# rcz80test_v1.net
KiCad netlist of a schematic drawn in EAGLE
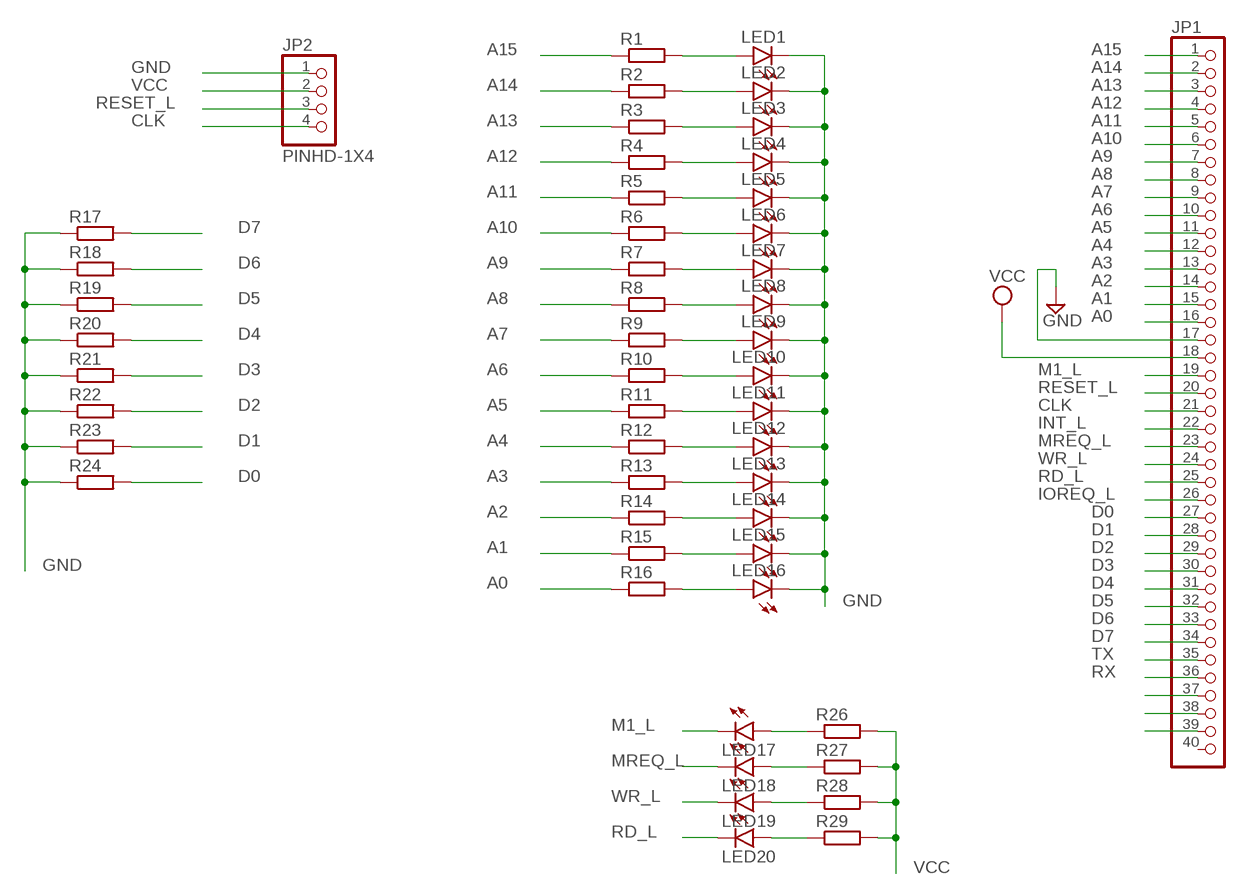
[diagram p0: schematic, sheet 1]

(export (version "E")
  (design (tool "Eeschema 10.0.6"))
  (components
    (comp (ref "JP1")
      (value "PINHD-1X40")
      (footprint "eagle-import:1X40")
      (libsource (lib "eagle-import") (part "PINHD-1X40"))
    )
    (comp (ref "JP2")
      (value "PINHD-1X4")
      (footprint "eagle-import:1X04")
      (libsource (lib "eagle-import") (part "PINHD-1X4"))
    )
    (comp (ref "LED1")
      (value "LED3MM")
      (footprint "eagle-import:LED3MM")
      (libsource (lib "eagle-import") (part "LED3MM"))
    )
    (comp (ref "LED2")
      (value "LED3MM")
      (footprint "eagle-import:LED3MM")
      (libsource (lib "eagle-import") (part "LED3MM"))
    )
    (comp (ref "LED3")
      (value "LED3MM")
      (footprint "eagle-import:LED3MM")
      (libsource (lib "eagle-import") (part "LED3MM"))
    )
    (comp (ref "LED4")
      (value "LED3MM")
      (footprint "eagle-import:LED3MM")
      (libsource (lib "eagle-import") (part "LED3MM"))
    )
    (comp (ref "LED5")
      (value "LED3MM")
      (footprint "eagle-import:LED3MM")
      (libsource (lib "eagle-import") (part "LED3MM"))
    )
    (comp (ref "LED6")
      (value "LED3MM")
      (footprint "eagle-import:LED3MM")
      (libsource (lib "eagle-import") (part "LED3MM"))
    )
    (comp (ref "LED7")
      (value "LED3MM")
      (footprint "eagle-import:LED3MM")
      (libsource (lib "eagle-import") (part "LED3MM"))
    )
    (comp (ref "LED8")
      (value "LED3MM")
      (footprint "eagle-import:LED3MM")
      (libsource (lib "eagle-import") (part "LED3MM"))
    )
    (comp (ref "LED9")
      (value "LED3MM")
      (footprint "eagle-import:LED3MM")
      (libsource (lib "eagle-import") (part "LED3MM"))
    )
    (comp (ref "LED10")
      (value "LED3MM")
      (footprint "eagle-import:LED3MM")
      (libsource (lib "eagle-import") (part "LED3MM"))
    )
    (comp (ref "LED11")
      (value "LED3MM")
      (footprint "eagle-import:LED3MM")
      (libsource (lib "eagle-import") (part "LED3MM"))
    )
    (comp (ref "LED12")
      (value "LED3MM")
      (footprint "eagle-import:LED3MM")
      (libsource (lib "eagle-import") (part "LED3MM"))
    )
    (comp (ref "LED13")
      (value "LED3MM")
      (footprint "eagle-import:LED3MM")
      (libsource (lib "eagle-import") (part "LED3MM"))
    )
    (comp (ref "LED14")
      (value "LED3MM")
      (footprint "eagle-import:LED3MM")
      (libsource (lib "eagle-import") (part "LED3MM"))
    )
    (comp (ref "LED15")
      (value "LED3MM")
      (footprint "eagle-import:LED3MM")
      (libsource (lib "eagle-import") (part "LED3MM"))
    )
    (comp (ref "LED16")
      (value "LED3MM")
      (footprint "eagle-import:LED3MM")
      (libsource (lib "eagle-import") (part "LED3MM"))
    )
    (comp (ref "LED17")
      (value "LED3MM")
      (footprint "eagle-import:LED3MM")
      (libsource (lib "eagle-import") (part "LED3MM"))
    )
    (comp (ref "LED18")
      (value "LED3MM")
      (footprint "eagle-import:LED3MM")
      (libsource (lib "eagle-import") (part "LED3MM"))
    )
    (comp (ref "LED19")
      (value "LED3MM")
      (footprint "eagle-import:LED3MM")
      (libsource (lib "eagle-import") (part "LED3MM"))
    )
    (comp (ref "LED20")
      (value "LED3MM")
      (footprint "eagle-import:LED3MM")
      (libsource (lib "eagle-import") (part "LED3MM"))
    )
    (comp (ref "R1")
      (value "R-EU_0204/7")
      (footprint "eagle-import:0204_7")
      (libsource (lib "eagle-import") (part "R-EU_0204/7"))
    )
    (comp (ref "R2")
      (value "R-EU_0204/7")
      (footprint "eagle-import:0204_7")
      (libsource (lib "eagle-import") (part "R-EU_0204/7"))
    )
    (comp (ref "R3")
      (value "R-EU_0204/7")
      (footprint "eagle-import:0204_7")
      (libsource (lib "eagle-import") (part "R-EU_0204/7"))
    )
    (comp (ref "R4")
      (value "R-EU_0204/7")
      (footprint "eagle-import:0204_7")
      (libsource (lib "eagle-import") (part "R-EU_0204/7"))
    )
    (comp (ref "R5")
      (value "R-EU_0204/7")
      (footprint "eagle-import:0204_7")
      (libsource (lib "eagle-import") (part "R-EU_0204/7"))
    )
    (comp (ref "R6")
      (value "R-EU_0204/7")
      (footprint "eagle-import:0204_7")
      (libsource (lib "eagle-import") (part "R-EU_0204/7"))
    )
    (comp (ref "R7")
      (value "R-EU_0204/7")
      (footprint "eagle-import:0204_7")
      (libsource (lib "eagle-import") (part "R-EU_0204/7"))
    )
    (comp (ref "R8")
      (value "R-EU_0204/7")
      (footprint "eagle-import:0204_7")
      (libsource (lib "eagle-import") (part "R-EU_0204/7"))
    )
    (comp (ref "R9")
      (value "R-EU_0204/7")
      (footprint "eagle-import:0204_7")
      (libsource (lib "eagle-import") (part "R-EU_0204/7"))
    )
    (comp (ref "R10")
      (value "R-EU_0204/7")
      (footprint "eagle-import:0204_7")
      (libsource (lib "eagle-import") (part "R-EU_0204/7"))
    )
    (comp (ref "R11")
      (value "R-EU_0204/7")
      (footprint "eagle-import:0204_7")
      (libsource (lib "eagle-import") (part "R-EU_0204/7"))
    )
    (comp (ref "R12")
      (value "R-EU_0204/7")
      (footprint "eagle-import:0204_7")
      (libsource (lib "eagle-import") (part "R-EU_0204/7"))
    )
    (comp (ref "R13")
      (value "R-EU_0204/7")
      (footprint "eagle-import:0204_7")
      (libsource (lib "eagle-import") (part "R-EU_0204/7"))
    )
    (comp (ref "R14")
      (value "R-EU_0204/7")
      (footprint "eagle-import:0204_7")
      (libsource (lib "eagle-import") (part "R-EU_0204/7"))
    )
    (comp (ref "R15")
      (value "R-EU_0204/7")
      (footprint "eagle-import:0204_7")
      (libsource (lib "eagle-import") (part "R-EU_0204/7"))
    )
    (comp (ref "R16")
      (value "R-EU_0204/7")
      (footprint "eagle-import:0204_7")
      (libsource (lib "eagle-import") (part "R-EU_0204/7"))
    )
    (comp (ref "R17")
      (value "R-EU_0204/7")
      (footprint "eagle-import:0204_7")
      (libsource (lib "eagle-import") (part "R-EU_0204/7"))
    )
    (comp (ref "R18")
      (value "R-EU_0204/7")
      (footprint "eagle-import:0204_7")
      (libsource (lib "eagle-import") (part "R-EU_0204/7"))
    )
    (comp (ref "R19")
      (value "R-EU_0204/7")
      (footprint "eagle-import:0204_7")
      (libsource (lib "eagle-import") (part "R-EU_0204/7"))
    )
    (comp (ref "R20")
      (value "R-EU_0204/7")
      (footprint "eagle-import:0204_7")
      (libsource (lib "eagle-import") (part "R-EU_0204/7"))
    )
    (comp (ref "R21")
      (value "R-EU_0204/7")
      (footprint "eagle-import:0204_7")
      (libsource (lib "eagle-import") (part "R-EU_0204/7"))
    )
    (comp (ref "R22")
      (value "R-EU_0204/7")
      (footprint "eagle-import:0204_7")
      (libsource (lib "eagle-import") (part "R-EU_0204/7"))
    )
    (comp (ref "R23")
      (value "R-EU_0204/7")
      (footprint "eagle-import:0204_7")
      (libsource (lib "eagle-import") (part "R-EU_0204/7"))
    )
    (comp (ref "R24")
      (value "R-EU_0204/7")
      (footprint "eagle-import:0204_7")
      (libsource (lib "eagle-import") (part "R-EU_0204/7"))
    )
    (comp (ref "R26")
      (value "R-EU_0204/7")
      (footprint "eagle-import:0204_7")
      (libsource (lib "eagle-import") (part "R-EU_0204/7"))
    )
    (comp (ref "R27")
      (value "R-EU_0204/7")
      (footprint "eagle-import:0204_7")
      (libsource (lib "eagle-import") (part "R-EU_0204/7"))
    )
    (comp (ref "R28")
      (value "R-EU_0204/7")
      (footprint "eagle-import:0204_7")
      (libsource (lib "eagle-import") (part "R-EU_0204/7"))
    )
    (comp (ref "R29")
      (value "R-EU_0204/7")
      (footprint "eagle-import:0204_7")
      (libsource (lib "eagle-import") (part "R-EU_0204/7"))
    )
  )
  (nets
    (net (code "1") (name "/A0") (class "Default")
      (node (ref "JP1") (pin "16") (pinfunction "16_16") (pintype "passive"))
      (node (ref "R16") (pin "1") (pinfunction "1_1") (pintype "passive"))
    )
    (net (code "2") (name "/A1") (class "Default")
      (node (ref "JP1") (pin "15") (pinfunction "15_15") (pintype "passive"))
      (node (ref "R15") (pin "1") (pinfunction "1_1") (pintype "passive"))
    )
    (net (code "3") (name "/A2") (class "Default")
      (node (ref "JP1") (pin "14") (pinfunction "14_14") (pintype "passive"))
      (node (ref "R14") (pin "1") (pinfunction "1_1") (pintype "passive"))
    )
    (net (code "4") (name "/A3") (class "Default")
      (node (ref "JP1") (pin "13") (pinfunction "13_13") (pintype "passive"))
      (node (ref "R13") (pin "1") (pinfunction "1_1") (pintype "passive"))
    )
    (net (code "5") (name "/A4") (class "Default")
      (node (ref "JP1") (pin "12") (pinfunction "12_12") (pintype "passive"))
      (node (ref "R12") (pin "1") (pinfunction "1_1") (pintype "passive"))
    )
    (net (code "6") (name "/A5") (class "Default")
      (node (ref "JP1") (pin "11") (pinfunction "11_11") (pintype "passive"))
      (node (ref "R11") (pin "1") (pinfunction "1_1") (pintype "passive"))
    )
    (net (code "7") (name "/A6") (class "Default")
      (node (ref "JP1") (pin "10") (pinfunction "10_10") (pintype "passive"))
      (node (ref "R10") (pin "1") (pinfunction "1_1") (pintype "passive"))
    )
    (net (code "8") (name "/A7") (class "Default")
      (node (ref "JP1") (pin "9") (pinfunction "9_9") (pintype "passive"))
      (node (ref "R9") (pin "1") (pinfunction "1_1") (pintype "passive"))
    )
    (net (code "9") (name "/A8") (class "Default")
      (node (ref "JP1") (pin "8") (pinfunction "8_8") (pintype "passive"))
      (node (ref "R8") (pin "1") (pinfunction "1_1") (pintype "passive"))
    )
    (net (code "10") (name "/A9") (class "Default")
      (node (ref "JP1") (pin "7") (pinfunction "7_7") (pintype "passive"))
      (node (ref "R7") (pin "1") (pinfunction "1_1") (pintype "passive"))
    )
    (net (code "11") (name "/A10") (class "Default")
      (node (ref "JP1") (pin "6") (pinfunction "6_6") (pintype "passive"))
      (node (ref "R6") (pin "1") (pinfunction "1_1") (pintype "passive"))
    )
    (net (code "12") (name "/A11") (class "Default")
      (node (ref "JP1") (pin "5") (pinfunction "5_5") (pintype "passive"))
      (node (ref "R5") (pin "1") (pinfunction "1_1") (pintype "passive"))
    )
    (net (code "13") (name "/A12") (class "Default")
      (node (ref "JP1") (pin "4") (pinfunction "4_4") (pintype "passive"))
      (node (ref "R4") (pin "1") (pinfunction "1_1") (pintype "passive"))
    )
    (net (code "14") (name "/A13") (class "Default")
      (node (ref "JP1") (pin "3") (pinfunction "3_3") (pintype "passive"))
      (node (ref "R3") (pin "1") (pinfunction "1_1") (pintype "passive"))
    )
    (net (code "15") (name "/A14") (class "Default")
      (node (ref "JP1") (pin "2") (pinfunction "2_2") (pintype "passive"))
      (node (ref "R2") (pin "1") (pinfunction "1_1") (pintype "passive"))
    )
    (net (code "16") (name "/A15") (class "Default")
      (node (ref "JP1") (pin "1") (pinfunction "1_1") (pintype "passive"))
      (node (ref "R1") (pin "1") (pinfunction "1_1") (pintype "passive"))
    )
    (net (code "17") (name "/CLK") (class "Default")
      (node (ref "JP1") (pin "21") (pinfunction "21_21") (pintype "passive"))
      (node (ref "JP2") (pin "4") (pinfunction "4_4") (pintype "passive"))
    )
    (net (code "18") (name "/D0") (class "Default")
      (node (ref "JP1") (pin "27") (pinfunction "27_27") (pintype "passive"))
      (node (ref "R24") (pin "2") (pinfunction "2_2") (pintype "passive"))
    )
    (net (code "19") (name "/D1") (class "Default")
      (node (ref "JP1") (pin "28") (pinfunction "28_28") (pintype "passive"))
      (node (ref "R23") (pin "2") (pinfunction "2_2") (pintype "passive"))
    )
    (net (code "20") (name "/D2") (class "Default")
      (node (ref "JP1") (pin "29") (pinfunction "29_29") (pintype "passive"))
      (node (ref "R22") (pin "2") (pinfunction "2_2") (pintype "passive"))
    )
    (net (code "21") (name "/D3") (class "Default")
      (node (ref "JP1") (pin "30") (pinfunction "30_30") (pintype "passive"))
      (node (ref "R21") (pin "2") (pinfunction "2_2") (pintype "passive"))
    )
    (net (code "22") (name "/D4") (class "Default")
      (node (ref "JP1") (pin "31") (pinfunction "31_31") (pintype "passive"))
      (node (ref "R20") (pin "2") (pinfunction "2_2") (pintype "passive"))
    )
    (net (code "23") (name "/D5") (class "Default")
      (node (ref "JP1") (pin "32") (pinfunction "32_32") (pintype "passive"))
      (node (ref "R19") (pin "2") (pinfunction "2_2") (pintype "passive"))
    )
    (net (code "24") (name "/D6") (class "Default")
      (node (ref "JP1") (pin "33") (pinfunction "33_33") (pintype "passive"))
      (node (ref "R18") (pin "2") (pinfunction "2_2") (pintype "passive"))
    )
    (net (code "25") (name "/D7") (class "Default")
      (node (ref "JP1") (pin "34") (pinfunction "34_34") (pintype "passive"))
      (node (ref "R17") (pin "2") (pinfunction "2_2") (pintype "passive"))
    )
    (net (code "26") (name "/INT_L") (class "Default")
      (node (ref "JP1") (pin "22") (pinfunction "22_22") (pintype "passive"))
    )
    (net (code "27") (name "/IOREQ_L") (class "Default")
      (node (ref "JP1") (pin "26") (pinfunction "26_26") (pintype "passive"))
    )
    (net (code "28") (name "/M1_L") (class "Default")
      (node (ref "JP1") (pin "19") (pinfunction "19_19") (pintype "passive"))
      (node (ref "LED17") (pin "K") (pinfunction "C_K") (pintype "passive"))
    )
    (net (code "29") (name "/MREQ_L") (class "Default")
      (node (ref "JP1") (pin "23") (pinfunction "23_23") (pintype "passive"))
      (node (ref "LED18") (pin "K") (pinfunction "C_K") (pintype "passive"))
    )
    (net (code "30") (name "/RD_L") (class "Default")
      (node (ref "JP1") (pin "25") (pinfunction "25_25") (pintype "passive"))
      (node (ref "LED20") (pin "K") (pinfunction "C_K") (pintype "passive"))
    )
    (net (code "31") (name "/RESET_L") (class "Default")
      (node (ref "JP1") (pin "20") (pinfunction "20_20") (pintype "passive"))
      (node (ref "JP2") (pin "3") (pinfunction "3_3") (pintype "passive"))
    )
    (net (code "32") (name "/RX") (class "Default")
      (node (ref "JP1") (pin "36") (pinfunction "36_36") (pintype "passive"))
    )
    (net (code "33") (name "/TX") (class "Default")
      (node (ref "JP1") (pin "35") (pinfunction "35_35") (pintype "passive"))
    )
    (net (code "34") (name "/WR_L") (class "Default")
      (node (ref "JP1") (pin "24") (pinfunction "24_24") (pintype "passive"))
      (node (ref "LED19") (pin "K") (pinfunction "C_K") (pintype "passive"))
    )
    (net (code "35") (name "GND") (class "Default")
      (node (ref "JP1") (pin "17") (pinfunction "17_17") (pintype "passive"))
      (node (ref "JP2") (pin "1") (pinfunction "1_1") (pintype "passive"))
      (node (ref "LED1") (pin "K") (pinfunction "C_K") (pintype "passive"))
      (node (ref "LED10") (pin "K") (pinfunction "C_K") (pintype "passive"))
      (node (ref "LED11") (pin "K") (pinfunction "C_K") (pintype "passive"))
      (node (ref "LED12") (pin "K") (pinfunction "C_K") (pintype "passive"))
      (node (ref "LED13") (pin "K") (pinfunction "C_K") (pintype "passive"))
      (node (ref "LED14") (pin "K") (pinfunction "C_K") (pintype "passive"))
      (node (ref "LED15") (pin "K") (pinfunction "C_K") (pintype "passive"))
      (node (ref "LED16") (pin "K") (pinfunction "C_K") (pintype "passive"))
      (node (ref "LED2") (pin "K") (pinfunction "C_K") (pintype "passive"))
      (node (ref "LED3") (pin "K") (pinfunction "C_K") (pintype "passive"))
      (node (ref "LED4") (pin "K") (pinfunction "C_K") (pintype "passive"))
      (node (ref "LED5") (pin "K") (pinfunction "C_K") (pintype "passive"))
      (node (ref "LED6") (pin "K") (pinfunction "C_K") (pintype "passive"))
      (node (ref "LED7") (pin "K") (pinfunction "C_K") (pintype "passive"))
      (node (ref "LED8") (pin "K") (pinfunction "C_K") (pintype "passive"))
      (node (ref "LED9") (pin "K") (pinfunction "C_K") (pintype "passive"))
      (node (ref "R17") (pin "1") (pinfunction "1_1") (pintype "passive"))
      (node (ref "R18") (pin "1") (pinfunction "1_1") (pintype "passive"))
      (node (ref "R19") (pin "1") (pinfunction "1_1") (pintype "passive"))
      (node (ref "R20") (pin "1") (pinfunction "1_1") (pintype "passive"))
      (node (ref "R21") (pin "1") (pinfunction "1_1") (pintype "passive"))
      (node (ref "R22") (pin "1") (pinfunction "1_1") (pintype "passive"))
      (node (ref "R23") (pin "1") (pinfunction "1_1") (pintype "passive"))
      (node (ref "R24") (pin "1") (pinfunction "1_1") (pintype "passive"))
    )
    (net (code "36") (name "Net-(LED1-PadA)") (class "Default")
      (node (ref "LED1") (pin "A") (pinfunction "A_A") (pintype "passive"))
      (node (ref "R1") (pin "2") (pinfunction "2_2") (pintype "passive"))
    )
    (net (code "37") (name "Net-(LED2-PadA)") (class "Default")
      (node (ref "LED2") (pin "A") (pinfunction "A_A") (pintype "passive"))
      (node (ref "R2") (pin "2") (pinfunction "2_2") (pintype "passive"))
    )
    (net (code "38") (name "Net-(LED3-PadA)") (class "Default")
      (node (ref "LED3") (pin "A") (pinfunction "A_A") (pintype "passive"))
      (node (ref "R3") (pin "2") (pinfunction "2_2") (pintype "passive"))
    )
    (net (code "39") (name "Net-(LED4-PadA)") (class "Default")
      (node (ref "LED4") (pin "A") (pinfunction "A_A") (pintype "passive"))
      (node (ref "R4") (pin "2") (pinfunction "2_2") (pintype "passive"))
    )
    (net (code "40") (name "Net-(LED5-PadA)") (class "Default")
      (node (ref "LED5") (pin "A") (pinfunction "A_A") (pintype "passive"))
      (node (ref "R5") (pin "2") (pinfunction "2_2") (pintype "passive"))
    )
    (net (code "41") (name "Net-(LED6-PadA)") (class "Default")
      (node (ref "LED6") (pin "A") (pinfunction "A_A") (pintype "passive"))
      (node (ref "R6") (pin "2") (pinfunction "2_2") (pintype "passive"))
    )
    (net (code "42") (name "Net-(LED7-PadA)") (class "Default")
      (node (ref "LED7") (pin "A") (pinfunction "A_A") (pintype "passive"))
      (node (ref "R7") (pin "2") (pinfunction "2_2") (pintype "passive"))
    )
    (net (code "43") (name "Net-(LED8-PadA)") (class "Default")
      (node (ref "LED8") (pin "A") (pinfunction "A_A") (pintype "passive"))
      (node (ref "R8") (pin "2") (pinfunction "2_2") (pintype "passive"))
    )
    (net (code "44") (name "Net-(LED9-PadA)") (class "Default")
      (node (ref "LED9") (pin "A") (pinfunction "A_A") (pintype "passive"))
      (node (ref "R9") (pin "2") (pinfunction "2_2") (pintype "passive"))
    )
    (net (code "45") (name "Net-(LED10-PadA)") (class "Default")
      (node (ref "LED10") (pin "A") (pinfunction "A_A") (pintype "passive"))
      (node (ref "R10") (pin "2") (pinfunction "2_2") (pintype "passive"))
    )
    (net (code "46") (name "Net-(LED11-PadA)") (class "Default")
      (node (ref "LED11") (pin "A") (pinfunction "A_A") (pintype "passive"))
      (node (ref "R11") (pin "2") (pinfunction "2_2") (pintype "passive"))
    )
    (net (code "47") (name "Net-(LED12-PadA)") (class "Default")
      (node (ref "LED12") (pin "A") (pinfunction "A_A") (pintype "passive"))
      (node (ref "R12") (pin "2") (pinfunction "2_2") (pintype "passive"))
    )
    (net (code "48") (name "Net-(LED13-PadA)") (class "Default")
      (node (ref "LED13") (pin "A") (pinfunction "A_A") (pintype "passive"))
      (node (ref "R13") (pin "2") (pinfunction "2_2") (pintype "passive"))
    )
    (net (code "49") (name "Net-(LED14-PadA)") (class "Default")
      (node (ref "LED14") (pin "A") (pinfunction "A_A") (pintype "passive"))
      (node (ref "R14") (pin "2") (pinfunction "2_2") (pintype "passive"))
    )
    (net (code "50") (name "Net-(LED15-PadA)") (class "Default")
      (node (ref "LED15") (pin "A") (pinfunction "A_A") (pintype "passive"))
      (node (ref "R15") (pin "2") (pinfunction "2_2") (pintype "passive"))
    )
    (net (code "51") (name "Net-(LED16-PadA)") (class "Default")
      (node (ref "LED16") (pin "A") (pinfunction "A_A") (pintype "passive"))
      (node (ref "R16") (pin "2") (pinfunction "2_2") (pintype "passive"))
    )
    (net (code "52") (name "Net-(LED17-PadA)") (class "Default")
      (node (ref "LED17") (pin "A") (pinfunction "A_A") (pintype "passive"))
      (node (ref "R26") (pin "1") (pinfunction "1_1") (pintype "passive"))
    )
    (net (code "53") (name "Net-(LED18-PadA)") (class "Default")
      (node (ref "LED18") (pin "A") (pinfunction "A_A") (pintype "passive"))
      (node (ref "R27") (pin "1") (pinfunction "1_1") (pintype "passive"))
    )
    (net (code "54") (name "Net-(LED19-PadA)") (class "Default")
      (node (ref "LED19") (pin "A") (pinfunction "A_A") (pintype "passive"))
      (node (ref "R28") (pin "1") (pinfunction "1_1") (pintype "passive"))
    )
    (net (code "55") (name "Net-(LED20-PadA)") (class "Default")
      (node (ref "LED20") (pin "A") (pinfunction "A_A") (pintype "passive"))
      (node (ref "R29") (pin "1") (pinfunction "1_1") (pintype "passive"))
    )
    (net (code "56") (name "VCC") (class "Default")
      (node (ref "JP1") (pin "18") (pinfunction "18_18") (pintype "passive"))
      (node (ref "JP2") (pin "2") (pinfunction "2_2") (pintype "passive"))
      (node (ref "R26") (pin "2") (pinfunction "2_2") (pintype "passive"))
      (node (ref "R27") (pin "2") (pinfunction "2_2") (pintype "passive"))
      (node (ref "R28") (pin "2") (pinfunction "2_2") (pintype "passive"))
      (node (ref "R29") (pin "2") (pinfunction "2_2") (pintype "passive"))
    )
    (net (code "57") (name "unconnected-(JP1-Pad37)") (class "Default")
      (node (ref "JP1") (pin "37") (pinfunction "37_37") (pintype "passive"))
    )
    (net (code "58") (name "unconnected-(JP1-Pad38)") (class "Default")
      (node (ref "JP1") (pin "38") (pinfunction "38_38") (pintype "passive"))
    )
    (net (code "59") (name "unconnected-(JP1-Pad39)") (class "Default")
      (node (ref "JP1") (pin "39") (pinfunction "39_39") (pintype "passive"))
    )
    (net (code "60") (name "unconnected-(JP1-Pad40)") (class "Default")
      (node (ref "JP1") (pin "40") (pinfunction "40_40") (pintype "passive"))
    )
  )
)
